# Motorcontroller.net
KiCad netlist of a schematic drawn in EAGLE
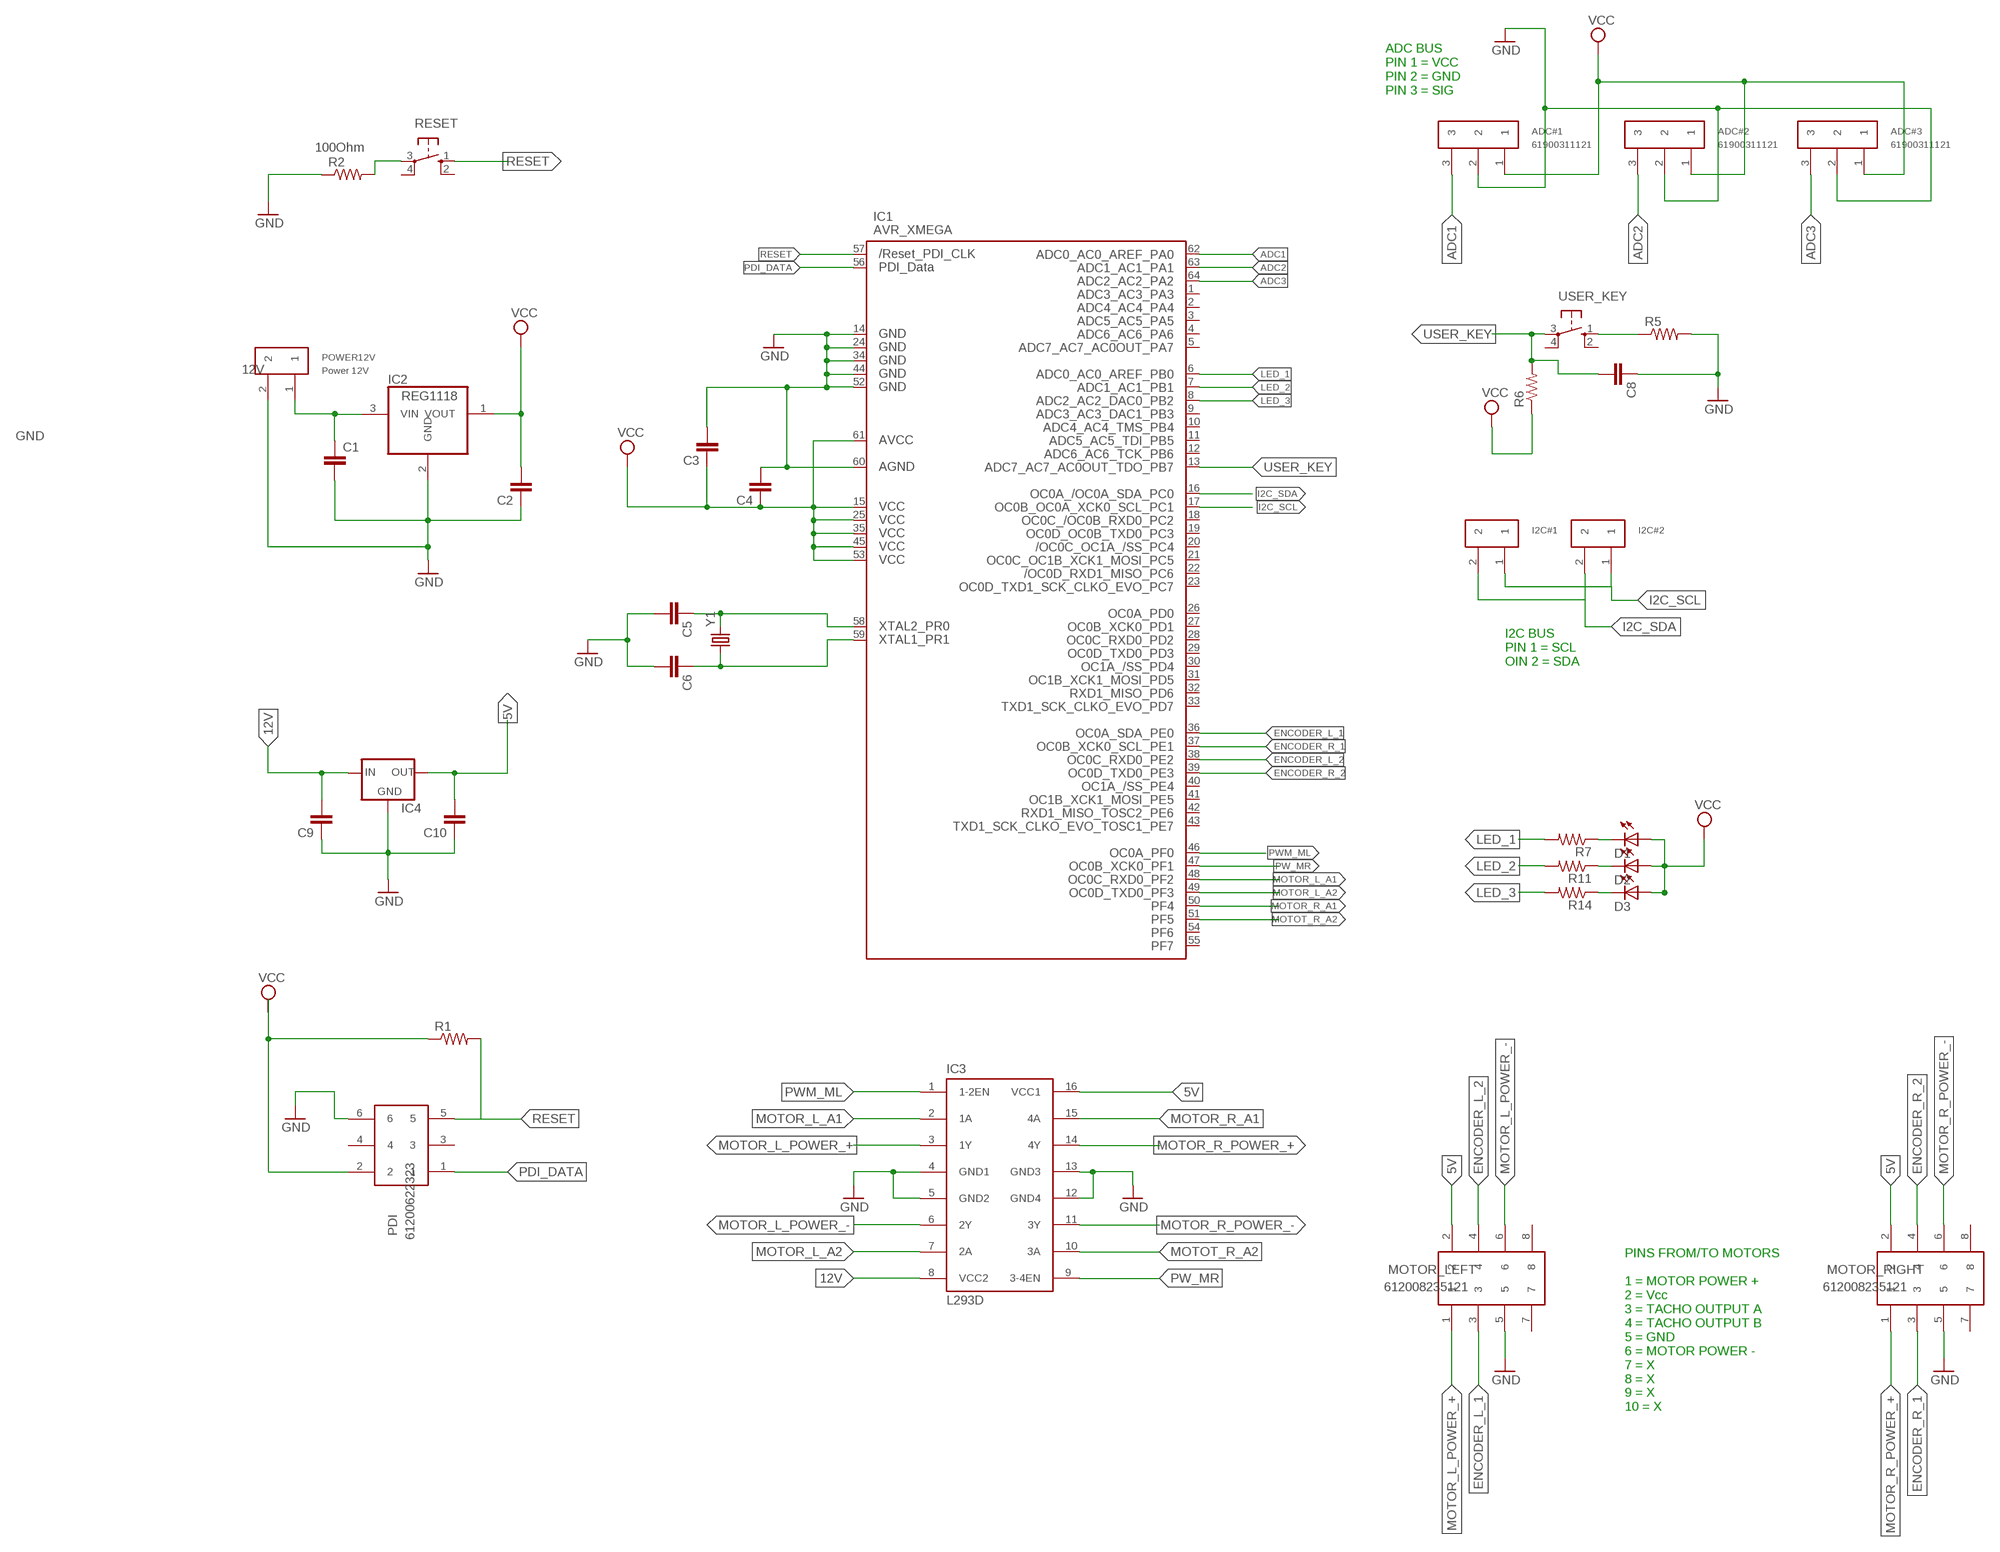
[diagram p0: schematic, sheet 1]

(export (version "E")
  (design (tool "Eeschema 10.0.6"))
  (components
    (comp (ref "ADC#1")
      (value "61900311121")
      (footprint "eagle-import:61900311121")
      (libsource (lib "eagle-import") (part "61900311121"))
    )
    (comp (ref "ADC#2")
      (value "61900311121")
      (footprint "eagle-import:61900311121")
      (libsource (lib "eagle-import") (part "61900311121"))
    )
    (comp (ref "ADC#3")
      (value "61900311121")
      (footprint "eagle-import:61900311121")
      (libsource (lib "eagle-import") (part "61900311121"))
    )
    (comp (ref "C1")
      (value "CAP1206")
      (footprint "eagle-import:1206")
      (libsource (lib "eagle-import") (part "CAP1206"))
    )
    (comp (ref "C2")
      (value "CAP1206")
      (footprint "eagle-import:1206")
      (libsource (lib "eagle-import") (part "CAP1206"))
    )
    (comp (ref "C3")
      (value "CAP1206")
      (footprint "eagle-import:1206")
      (libsource (lib "eagle-import") (part "CAP1206"))
    )
    (comp (ref "C4")
      (value "CAP1206")
      (footprint "eagle-import:1206")
      (libsource (lib "eagle-import") (part "CAP1206"))
    )
    (comp (ref "C5")
      (value "CAP1206")
      (footprint "eagle-import:1206")
      (libsource (lib "eagle-import") (part "CAP1206"))
    )
    (comp (ref "C6")
      (value "CAP1206")
      (footprint "eagle-import:1206")
      (libsource (lib "eagle-import") (part "CAP1206"))
    )
    (comp (ref "C8")
      (value "CAP1206")
      (footprint "eagle-import:1206")
      (libsource (lib "eagle-import") (part "CAP1206"))
    )
    (comp (ref "C9")
      (value "CAP1206")
      (footprint "eagle-import:1206")
      (libsource (lib "eagle-import") (part "CAP1206"))
    )
    (comp (ref "C10")
      (value "CAP1206")
      (footprint "eagle-import:1206")
      (libsource (lib "eagle-import") (part "CAP1206"))
    )
    (comp (ref "D1")
      (value "LEDSML0805")
      (footprint "eagle-import:SML0805")
      (libsource (lib "eagle-import") (part "LEDSML0805"))
    )
    (comp (ref "D2")
      (value "LEDSML0805")
      (footprint "eagle-import:SML0805")
      (libsource (lib "eagle-import") (part "LEDSML0805"))
    )
    (comp (ref "D3")
      (value "LEDSML0805")
      (footprint "eagle-import:SML0805")
      (libsource (lib "eagle-import") (part "LEDSML0805"))
    )
    (comp (ref "I2C#1")
      (value "61900211121")
      (footprint "eagle-import:61900211121")
      (libsource (lib "eagle-import") (part "61900211121"))
    )
    (comp (ref "I2C#2")
      (value "61900211121")
      (footprint "eagle-import:61900211121")
      (libsource (lib "eagle-import") (part "61900211121"))
    )
    (comp (ref "IC1")
      (value "AVR_XMEGA")
      (footprint "eagle-import:TQFP64")
      (libsource (lib "eagle-import") (part "AVR_XMEGA_A3_"))
    )
    (comp (ref "IC2")
      (value "REG1118")
      (footprint "eagle-import:SOT223")
      (fields (field (name "MPN") "REG1118-2.85/2K5G4"))
      (libsource (lib "eagle-import") (part "REG1118"))
    )
    (comp (ref "IC3")
      (value "L293D")
      (footprint "eagle-import:DIL16")
      (libsource (lib "eagle-import") (part "L293D"))
    )
    (comp (ref "IC4")
      (value "V_REG_78XX-TO-220")
      (footprint "eagle-import:TO-220-ALT")
      (libsource (lib "eagle-import") (part "V_REG_78XX-TO-220"))
    )
    (comp (ref "MOTOR_LEFT")
      (value "612008235121")
      (footprint "eagle-import:612008235121")
      (libsource (lib "eagle-import") (part "612008235121"))
    )
    (comp (ref "MOTOR_RIGHT")
      (value "612008235121")
      (footprint "eagle-import:612008235121")
      (libsource (lib "eagle-import") (part "612008235121"))
    )
    (comp (ref "PDI")
      (value "61200622323")
      (footprint "eagle-import:61200622323")
      (libsource (lib "eagle-import") (part "61200622323"))
    )
    (comp (ref "POWER12V")
      (value "Power 12V")
      (footprint "eagle-import:61900211121")
      (libsource (lib "eagle-import") (part "61900211121"))
    )
    (comp (ref "R1")
      (value "RESISTOR1206")
      (footprint "eagle-import:1206")
      (libsource (lib "eagle-import") (part "RESISTOR1206"))
    )
    (comp (ref "R2")
      (value "100Ohm")
      (footprint "eagle-import:1206")
      (libsource (lib "eagle-import") (part "SparkFun-Resistors_RESISTOR1206"))
    )
    (comp (ref "R5")
      (value "RESISTOR1206")
      (footprint "eagle-import:1206")
      (libsource (lib "eagle-import") (part "SparkFun-Resistors_RESISTOR1206"))
    )
    (comp (ref "R6")
      (value "RESISTOR1206")
      (footprint "eagle-import:1206")
      (libsource (lib "eagle-import") (part "SparkFun-Resistors_RESISTOR1206"))
    )
    (comp (ref "R7")
      (value "RESISTOR1206")
      (footprint "eagle-import:1206")
      (libsource (lib "eagle-import") (part "SparkFun-Resistors_RESISTOR1206"))
    )
    (comp (ref "R11")
      (value "RESISTOR1206")
      (footprint "eagle-import:1206")
      (libsource (lib "eagle-import") (part "SparkFun-Resistors_RESISTOR1206"))
    )
    (comp (ref "R14")
      (value "RESISTOR1206")
      (footprint "eagle-import:1206")
      (libsource (lib "eagle-import") (part "SparkFun-Resistors_RESISTOR1206"))
    )
    (comp (ref "RESET")
      (value "10-XX")
      (footprint "eagle-import:B3F-10XX")
      (fields (field (name "MPN") "B3F-1000"))
      (libsource (lib "eagle-import") (part "10-XX"))
    )
    (comp (ref "USER_KEY")
      (value "10-XX")
      (footprint "eagle-import:B3F-10XX")
      (fields (field (name "MPN") "B3F-1000"))
      (libsource (lib "eagle-import") (part "10-XX"))
    )
    (comp (ref "Y1")
      (value "CRYSTALHC49US")
      (footprint "eagle-import:HC49US")
      (libsource (lib "eagle-import") (part "CRYSTALHC49US"))
    )
  )
  (nets
    (net (code "1") (name "5V") (class "Default")
      (node (ref "C10") (pin "2") (pinfunction "2_2") (pintype "passive"))
      (node (ref "IC3") (pin "16") (pinfunction "VCC1_16") (pintype "power_in"))
      (node (ref "IC4") (pin "OUT") (pinfunction "OUT_OUT") (pintype "output"))
      (node (ref "MOTOR_LEFT") (pin "2") (pinfunction "2_2") (pintype "passive"))
      (node (ref "MOTOR_RIGHT") (pin "2") (pinfunction "2_2") (pintype "passive"))
    )
    (net (code "2") (name "12V") (class "Default")
      (node (ref "C1") (pin "1") (pinfunction "1_1") (pintype "passive"))
      (node (ref "C9") (pin "2") (pinfunction "2_2") (pintype "passive"))
      (node (ref "IC2") (pin "3") (pinfunction "VIN_3") (pintype "input"))
      (node (ref "IC3") (pin "8") (pinfunction "VCC2_8") (pintype "power_in"))
      (node (ref "IC4") (pin "IN") (pinfunction "IN_IN") (pintype "input"))
      (node (ref "POWER12V") (pin "1") (pinfunction "1_1") (pintype "bidirectional"))
    )
    (net (code "3") (name "ADC1") (class "Default")
      (node (ref "ADC#1") (pin "3") (pinfunction "3_3") (pintype "bidirectional"))
      (node (ref "IC1") (pin "62") (pinfunction "PA0_62") (pintype "bidirectional"))
    )
    (net (code "4") (name "ADC2") (class "Default")
      (node (ref "ADC#2") (pin "3") (pinfunction "3_3") (pintype "bidirectional"))
      (node (ref "IC1") (pin "63") (pinfunction "PA1_63") (pintype "bidirectional"))
    )
    (net (code "5") (name "ADC3") (class "Default")
      (node (ref "ADC#3") (pin "3") (pinfunction "3_3") (pintype "bidirectional"))
      (node (ref "IC1") (pin "64") (pinfunction "PA2_64") (pintype "bidirectional"))
    )
    (net (code "6") (name "ENCODER_L_1") (class "Default")
      (node (ref "IC1") (pin "36") (pinfunction "PE0_36") (pintype "bidirectional"))
      (node (ref "MOTOR_LEFT") (pin "3") (pinfunction "3_3") (pintype "passive"))
    )
    (net (code "7") (name "ENCODER_L_2") (class "Default")
      (node (ref "IC1") (pin "38") (pinfunction "PE2_38") (pintype "bidirectional"))
      (node (ref "MOTOR_LEFT") (pin "4") (pinfunction "4_4") (pintype "passive"))
    )
    (net (code "8") (name "ENCODER_R_1") (class "Default")
      (node (ref "IC1") (pin "37") (pinfunction "PE1_37") (pintype "bidirectional"))
      (node (ref "MOTOR_RIGHT") (pin "3") (pinfunction "3_3") (pintype "passive"))
    )
    (net (code "9") (name "ENCODER_R_2") (class "Default")
      (node (ref "IC1") (pin "39") (pinfunction "PE3_39") (pintype "bidirectional"))
      (node (ref "MOTOR_RIGHT") (pin "4") (pinfunction "4_4") (pintype "passive"))
    )
    (net (code "10") (name "GND") (class "Default")
      (node (ref "ADC#1") (pin "2") (pinfunction "2_2") (pintype "bidirectional"))
      (node (ref "ADC#2") (pin "2") (pinfunction "2_2") (pintype "bidirectional"))
      (node (ref "ADC#3") (pin "2") (pinfunction "2_2") (pintype "bidirectional"))
      (node (ref "C1") (pin "2") (pinfunction "2_2") (pintype "passive"))
      (node (ref "C10") (pin "1") (pinfunction "1_1") (pintype "passive"))
      (node (ref "C2") (pin "1") (pinfunction "1_1") (pintype "passive"))
      (node (ref "C3") (pin "2") (pinfunction "2_2") (pintype "passive"))
      (node (ref "C4") (pin "2") (pinfunction "2_2") (pintype "passive"))
      (node (ref "C5") (pin "2") (pinfunction "2_2") (pintype "passive"))
      (node (ref "C6") (pin "2") (pinfunction "2_2") (pintype "passive"))
      (node (ref "C8") (pin "1") (pinfunction "1_1") (pintype "passive"))
      (node (ref "C9") (pin "1") (pinfunction "1_1") (pintype "passive"))
      (node (ref "IC1") (pin "14") (pinfunction "GND1_14") (pintype "bidirectional"))
      (node (ref "IC1") (pin "24") (pinfunction "GND2_24") (pintype "bidirectional"))
      (node (ref "IC1") (pin "34") (pinfunction "GND3_34") (pintype "bidirectional"))
      (node (ref "IC1") (pin "44") (pinfunction "GND4_44") (pintype "bidirectional"))
      (node (ref "IC1") (pin "52") (pinfunction "GND5_52") (pintype "bidirectional"))
      (node (ref "IC1") (pin "60") (pinfunction "AGND_60") (pintype "bidirectional"))
      (node (ref "IC2") (pin "2") (pinfunction "GND_2") (pintype "power_in"))
      (node (ref "IC3") (pin "12") (pinfunction "GND4_12") (pintype "power_in"))
      (node (ref "IC3") (pin "13") (pinfunction "GND3_13") (pintype "power_in"))
      (node (ref "IC3") (pin "4") (pinfunction "GND1_4") (pintype "power_in"))
      (node (ref "IC3") (pin "5") (pinfunction "GND2_5") (pintype "power_in"))
      (node (ref "IC4") (pin "GND") (pinfunction "GND_GND") (pintype "input"))
      (node (ref "MOTOR_LEFT") (pin "5") (pinfunction "5_5") (pintype "passive"))
      (node (ref "MOTOR_RIGHT") (pin "5") (pinfunction "5_5") (pintype "passive"))
      (node (ref "PDI") (pin "6") (pinfunction "6_6") (pintype "passive"))
      (node (ref "POWER12V") (pin "2") (pinfunction "2_2") (pintype "bidirectional"))
      (node (ref "R2") (pin "1") (pinfunction "1_1") (pintype "passive"))
      (node (ref "R5") (pin "2") (pinfunction "2_2") (pintype "passive"))
    )
    (net (code "11") (name "I2C_SCL") (class "Default")
      (node (ref "I2C#1") (pin "1") (pinfunction "1_1") (pintype "bidirectional"))
      (node (ref "I2C#2") (pin "1") (pinfunction "1_1") (pintype "bidirectional"))
      (node (ref "IC1") (pin "17") (pinfunction "PC1_17") (pintype "bidirectional"))
    )
    (net (code "12") (name "I2C_SDA") (class "Default")
      (node (ref "I2C#1") (pin "2") (pinfunction "2_2") (pintype "bidirectional"))
      (node (ref "I2C#2") (pin "2") (pinfunction "2_2") (pintype "bidirectional"))
      (node (ref "IC1") (pin "16") (pinfunction "PC0_16") (pintype "bidirectional"))
    )
    (net (code "13") (name "LED_1") (class "Default")
      (node (ref "IC1") (pin "6") (pinfunction "PB0_6") (pintype "bidirectional"))
      (node (ref "R7") (pin "2") (pinfunction "2_2") (pintype "passive"))
    )
    (net (code "14") (name "LED_2") (class "Default")
      (node (ref "IC1") (pin "7") (pinfunction "PB1_7") (pintype "bidirectional"))
    )
    (net (code "15") (name "LED_3") (class "Default")
      (node (ref "IC1") (pin "8") (pinfunction "PB2_8") (pintype "bidirectional"))
    )
    (net (code "16") (name "MOTOR_L_A1") (class "Default")
      (node (ref "IC1") (pin "48") (pinfunction "PF2_48") (pintype "bidirectional"))
      (node (ref "IC3") (pin "2") (pinfunction "1A_2") (pintype "input"))
    )
    (net (code "17") (name "MOTOR_L_A2") (class "Default")
      (node (ref "IC1") (pin "49") (pinfunction "PF3_49") (pintype "bidirectional"))
      (node (ref "IC3") (pin "7") (pinfunction "2A_7") (pintype "input"))
    )
    (net (code "18") (name "MOTOR_L_POWER_+") (class "Default")
      (node (ref "IC3") (pin "3") (pinfunction "1Y_3") (pintype "output"))
      (node (ref "MOTOR_LEFT") (pin "1") (pinfunction "1_1") (pintype "passive"))
    )
    (net (code "19") (name "MOTOR_L_POWER_-") (class "Default")
      (node (ref "IC3") (pin "6") (pinfunction "2Y_6") (pintype "output"))
      (node (ref "MOTOR_LEFT") (pin "6") (pinfunction "6_6") (pintype "passive"))
    )
    (net (code "20") (name "MOTOR_R_A1") (class "Default")
      (node (ref "IC1") (pin "50") (pinfunction "PF4_50") (pintype "bidirectional"))
      (node (ref "IC3") (pin "15") (pinfunction "4A_15") (pintype "input"))
    )
    (net (code "21") (name "MOTOR_R_POWER_+") (class "Default")
      (node (ref "IC3") (pin "14") (pinfunction "4Y_14") (pintype "output"))
      (node (ref "MOTOR_RIGHT") (pin "1") (pinfunction "1_1") (pintype "passive"))
    )
    (net (code "22") (name "MOTOR_R_POWER_-") (class "Default")
      (node (ref "IC3") (pin "11") (pinfunction "3Y_11") (pintype "output"))
      (node (ref "MOTOR_RIGHT") (pin "6") (pinfunction "6_6") (pintype "passive"))
    )
    (net (code "23") (name "MOTOT_R_A2") (class "Default")
      (node (ref "IC1") (pin "51") (pinfunction "PF5_51") (pintype "bidirectional"))
      (node (ref "IC3") (pin "10") (pinfunction "3A_10") (pintype "input"))
    )
    (net (code "24") (name "Net-(D1-PadC)") (class "Default")
      (node (ref "D1") (pin "C") (pinfunction "C_C") (pintype "passive"))
      (node (ref "R7") (pin "1") (pinfunction "1_1") (pintype "passive"))
    )
    (net (code "25") (name "Net-(D2-PadC)") (class "Default")
      (node (ref "D2") (pin "C") (pinfunction "C_C") (pintype "passive"))
      (node (ref "R11") (pin "1") (pinfunction "1_1") (pintype "passive"))
    )
    (net (code "26") (name "Net-(D3-PadC)") (class "Default")
      (node (ref "D3") (pin "C") (pinfunction "C_C") (pintype "passive"))
      (node (ref "R14") (pin "1") (pinfunction "1_1") (pintype "passive"))
    )
    (net (code "27") (name "Net-(IC1-PR0)") (class "Default")
      (node (ref "C5") (pin "1") (pinfunction "1_1") (pintype "passive"))
      (node (ref "IC1") (pin "58") (pinfunction "PR0_58") (pintype "bidirectional"))
      (node (ref "Y1") (pin "2") (pinfunction "2_2") (pintype "passive"))
    )
    (net (code "28") (name "Net-(IC1-PR1)") (class "Default")
      (node (ref "C6") (pin "1") (pinfunction "1_1") (pintype "passive"))
      (node (ref "IC1") (pin "59") (pinfunction "PR1_59") (pintype "bidirectional"))
      (node (ref "Y1") (pin "1") (pinfunction "1_1") (pintype "passive"))
    )
    (net (code "29") (name "Net-(RESET-P)") (class "Default")
      (node (ref "R2") (pin "2") (pinfunction "2_2") (pintype "passive"))
      (node (ref "RESET") (pin "3") (pinfunction "P_3") (pintype "passive"))
    )
    (net (code "30") (name "Net-(USER_KEY-S)") (class "Default")
      (node (ref "R5") (pin "1") (pinfunction "1_1") (pintype "passive"))
      (node (ref "USER_KEY") (pin "1") (pinfunction "S_1") (pintype "passive"))
    )
    (net (code "31") (name "PDI_DATA") (class "Default")
      (node (ref "IC1") (pin "56") (pinfunction "PDI_DATA_56") (pintype "bidirectional"))
      (node (ref "PDI") (pin "1") (pinfunction "1_1") (pintype "passive"))
    )
    (net (code "32") (name "PWM_ML") (class "Default")
      (node (ref "IC1") (pin "46") (pinfunction "PF0_46") (pintype "bidirectional"))
      (node (ref "IC3") (pin "1") (pinfunction "1-2EN_1") (pintype "input"))
    )
    (net (code "33") (name "PW_MR") (class "Default")
      (node (ref "IC1") (pin "47") (pinfunction "PF1_47") (pintype "bidirectional"))
      (node (ref "IC3") (pin "9") (pinfunction "3-4EN_9") (pintype "input"))
    )
    (net (code "34") (name "RESET") (class "Default")
      (node (ref "IC1") (pin "57") (pinfunction "RESET_57") (pintype "bidirectional"))
      (node (ref "PDI") (pin "5") (pinfunction "5_5") (pintype "passive"))
      (node (ref "R1") (pin "2") (pinfunction "2_2") (pintype "passive"))
      (node (ref "RESET") (pin "1") (pinfunction "S_1") (pintype "passive"))
    )
    (net (code "35") (name "USER_KEY") (class "Default")
      (node (ref "C8") (pin "2") (pinfunction "2_2") (pintype "passive"))
      (node (ref "IC1") (pin "13") (pinfunction "PB7_13") (pintype "bidirectional"))
      (node (ref "R6") (pin "2") (pinfunction "2_2") (pintype "passive"))
      (node (ref "USER_KEY") (pin "3") (pinfunction "P_3") (pintype "passive"))
    )
    (net (code "36") (name "VCC") (class "Default")
      (node (ref "ADC#1") (pin "1") (pinfunction "1_1") (pintype "bidirectional"))
      (node (ref "ADC#2") (pin "1") (pinfunction "1_1") (pintype "bidirectional"))
      (node (ref "ADC#3") (pin "1") (pinfunction "1_1") (pintype "bidirectional"))
      (node (ref "C2") (pin "2") (pinfunction "2_2") (pintype "passive"))
      (node (ref "C3") (pin "1") (pinfunction "1_1") (pintype "passive"))
      (node (ref "C4") (pin "1") (pinfunction "1_1") (pintype "passive"))
      (node (ref "D1") (pin "A") (pinfunction "A_A") (pintype "passive"))
      (node (ref "D2") (pin "A") (pinfunction "A_A") (pintype "passive"))
      (node (ref "D3") (pin "A") (pinfunction "A_A") (pintype "passive"))
      (node (ref "IC1") (pin "15") (pinfunction "VCC1_15") (pintype "bidirectional"))
      (node (ref "IC1") (pin "25") (pinfunction "VCC2_25") (pintype "bidirectional"))
      (node (ref "IC1") (pin "35") (pinfunction "VCC3_35") (pintype "bidirectional"))
      (node (ref "IC1") (pin "45") (pinfunction "VCC4_45") (pintype "bidirectional"))
      (node (ref "IC1") (pin "53") (pinfunction "VCC5_53") (pintype "bidirectional"))
      (node (ref "IC1") (pin "61") (pinfunction "AVCC_61") (pintype "bidirectional"))
      (node (ref "IC2") (pin "1") (pinfunction "VOUT_1") (pintype "output"))
      (node (ref "PDI") (pin "2") (pinfunction "2_2") (pintype "passive"))
      (node (ref "R1") (pin "1") (pinfunction "1_1") (pintype "passive"))
      (node (ref "R6") (pin "1") (pinfunction "1_1") (pintype "passive"))
    )
    (net (code "37") (name "unconnected-(IC1-PA3-Pad1)") (class "Default")
      (node (ref "IC1") (pin "1") (pinfunction "PA3_1") (pintype "bidirectional"))
    )
    (net (code "38") (name "unconnected-(IC1-PA4-Pad2)") (class "Default")
      (node (ref "IC1") (pin "2") (pinfunction "PA4_2") (pintype "bidirectional"))
    )
    (net (code "39") (name "unconnected-(IC1-PA5-Pad3)") (class "Default")
      (node (ref "IC1") (pin "3") (pinfunction "PA5_3") (pintype "bidirectional"))
    )
    (net (code "40") (name "unconnected-(IC1-PA6-Pad4)") (class "Default")
      (node (ref "IC1") (pin "4") (pinfunction "PA6_4") (pintype "bidirectional"))
    )
    (net (code "41") (name "unconnected-(IC1-PA7-Pad5)") (class "Default")
      (node (ref "IC1") (pin "5") (pinfunction "PA7_5") (pintype "bidirectional"))
    )
    (net (code "42") (name "unconnected-(IC1-PB3-Pad9)") (class "Default")
      (node (ref "IC1") (pin "9") (pinfunction "PB3_9") (pintype "bidirectional"))
    )
    (net (code "43") (name "unconnected-(IC1-PB4-Pad10)") (class "Default")
      (node (ref "IC1") (pin "10") (pinfunction "PB4_10") (pintype "bidirectional"))
    )
    (net (code "44") (name "unconnected-(IC1-PB5-Pad11)") (class "Default")
      (node (ref "IC1") (pin "11") (pinfunction "PB5_11") (pintype "bidirectional"))
    )
    (net (code "45") (name "unconnected-(IC1-PB6-Pad12)") (class "Default")
      (node (ref "IC1") (pin "12") (pinfunction "PB6_12") (pintype "bidirectional"))
    )
    (net (code "46") (name "unconnected-(IC1-PC2-Pad18)") (class "Default")
      (node (ref "IC1") (pin "18") (pinfunction "PC2_18") (pintype "bidirectional"))
    )
    (net (code "47") (name "unconnected-(IC1-PC3-Pad19)") (class "Default")
      (node (ref "IC1") (pin "19") (pinfunction "PC3_19") (pintype "bidirectional"))
    )
    (net (code "48") (name "unconnected-(IC1-PC4-Pad20)") (class "Default")
      (node (ref "IC1") (pin "20") (pinfunction "PC4_20") (pintype "bidirectional"))
    )
    (net (code "49") (name "unconnected-(IC1-PC5-Pad21)") (class "Default")
      (node (ref "IC1") (pin "21") (pinfunction "PC5_21") (pintype "bidirectional"))
    )
    (net (code "50") (name "unconnected-(IC1-PC6-Pad22)") (class "Default")
      (node (ref "IC1") (pin "22") (pinfunction "PC6_22") (pintype "bidirectional"))
    )
    (net (code "51") (name "unconnected-(IC1-PC7-Pad23)") (class "Default")
      (node (ref "IC1") (pin "23") (pinfunction "PC7_23") (pintype "bidirectional"))
    )
    (net (code "52") (name "unconnected-(IC1-PD0-Pad26)") (class "Default")
      (node (ref "IC1") (pin "26") (pinfunction "PD0_26") (pintype "bidirectional"))
    )
    (net (code "53") (name "unconnected-(IC1-PD1-Pad27)") (class "Default")
      (node (ref "IC1") (pin "27") (pinfunction "PD1_27") (pintype "bidirectional"))
    )
    (net (code "54") (name "unconnected-(IC1-PD2-Pad28)") (class "Default")
      (node (ref "IC1") (pin "28") (pinfunction "PD2_28") (pintype "bidirectional"))
    )
    (net (code "55") (name "unconnected-(IC1-PD3-Pad29)") (class "Default")
      (node (ref "IC1") (pin "29") (pinfunction "PD3_29") (pintype "bidirectional"))
    )
    (net (code "56") (name "unconnected-(IC1-PD4-Pad30)") (class "Default")
      (node (ref "IC1") (pin "30") (pinfunction "PD4_30") (pintype "bidirectional"))
    )
    (net (code "57") (name "unconnected-(IC1-PD5-Pad31)") (class "Default")
      (node (ref "IC1") (pin "31") (pinfunction "PD5_31") (pintype "bidirectional"))
    )
    (net (code "58") (name "unconnected-(IC1-PD6-Pad32)") (class "Default")
      (node (ref "IC1") (pin "32") (pinfunction "PD6_32") (pintype "bidirectional"))
    )
    (net (code "59") (name "unconnected-(IC1-PD7-Pad33)") (class "Default")
      (node (ref "IC1") (pin "33") (pinfunction "PD7_33") (pintype "bidirectional"))
    )
    (net (code "60") (name "unconnected-(IC1-PE4-Pad40)") (class "Default")
      (node (ref "IC1") (pin "40") (pinfunction "PE4_40") (pintype "bidirectional"))
    )
    (net (code "61") (name "unconnected-(IC1-PE5-Pad41)") (class "Default")
      (node (ref "IC1") (pin "41") (pinfunction "PE5_41") (pintype "bidirectional"))
    )
    (net (code "62") (name "unconnected-(IC1-PE6-Pad42)") (class "Default")
      (node (ref "IC1") (pin "42") (pinfunction "PE6_42") (pintype "bidirectional"))
    )
    (net (code "63") (name "unconnected-(IC1-PE7-Pad43)") (class "Default")
      (node (ref "IC1") (pin "43") (pinfunction "PE7_43") (pintype "bidirectional"))
    )
    (net (code "64") (name "unconnected-(IC1-PF6-Pad54)") (class "Default")
      (node (ref "IC1") (pin "54") (pinfunction "PF6_54") (pintype "bidirectional"))
    )
    (net (code "65") (name "unconnected-(IC1-PF7-Pad55)") (class "Default")
      (node (ref "IC1") (pin "55") (pinfunction "PF7_55") (pintype "bidirectional"))
    )
    (net (code "66") (name "unconnected-(MOTOR_LEFT-Pad7)") (class "Default")
      (node (ref "MOTOR_LEFT") (pin "7") (pinfunction "7_7") (pintype "passive"))
    )
    (net (code "67") (name "unconnected-(MOTOR_LEFT-Pad8)") (class "Default")
      (node (ref "MOTOR_LEFT") (pin "8") (pinfunction "8_8") (pintype "passive"))
    )
    (net (code "68") (name "unconnected-(MOTOR_RIGHT-Pad7)") (class "Default")
      (node (ref "MOTOR_RIGHT") (pin "7") (pinfunction "7_7") (pintype "passive"))
    )
    (net (code "69") (name "unconnected-(MOTOR_RIGHT-Pad8)") (class "Default")
      (node (ref "MOTOR_RIGHT") (pin "8") (pinfunction "8_8") (pintype "passive"))
    )
    (net (code "70") (name "unconnected-(PDI-Pad3)") (class "Default")
      (node (ref "PDI") (pin "3") (pinfunction "3_3") (pintype "passive"))
    )
    (net (code "71") (name "unconnected-(PDI-Pad4)") (class "Default")
      (node (ref "PDI") (pin "4") (pinfunction "4_4") (pintype "passive"))
    )
    (net (code "72") (name "unconnected-(R11-Pad2)") (class "Default")
      (node (ref "R11") (pin "2") (pinfunction "2_2") (pintype "passive"))
    )
    (net (code "73") (name "unconnected-(R14-Pad2)") (class "Default")
      (node (ref "R14") (pin "2") (pinfunction "2_2") (pintype "passive"))
    )
    (net (code "74") (name "unconnected-(RESET-P1-Pad4)") (class "Default")
      (node (ref "RESET") (pin "4") (pinfunction "P1_4") (pintype "passive"))
    )
    (net (code "75") (name "unconnected-(RESET-S1-Pad2)") (class "Default")
      (node (ref "RESET") (pin "2") (pinfunction "S1_2") (pintype "passive"))
    )
    (net (code "76") (name "unconnected-(USER_KEY-P1-Pad4)") (class "Default")
      (node (ref "USER_KEY") (pin "4") (pinfunction "P1_4") (pintype "passive"))
    )
    (net (code "77") (name "unconnected-(USER_KEY-S1-Pad2)") (class "Default")
      (node (ref "USER_KEY") (pin "2") (pinfunction "S1_2") (pintype "passive"))
    )
  )
)
